# FInal_Board_Tesis_mini_4.net
KiCad netlist of a schematic drawn in EAGLE
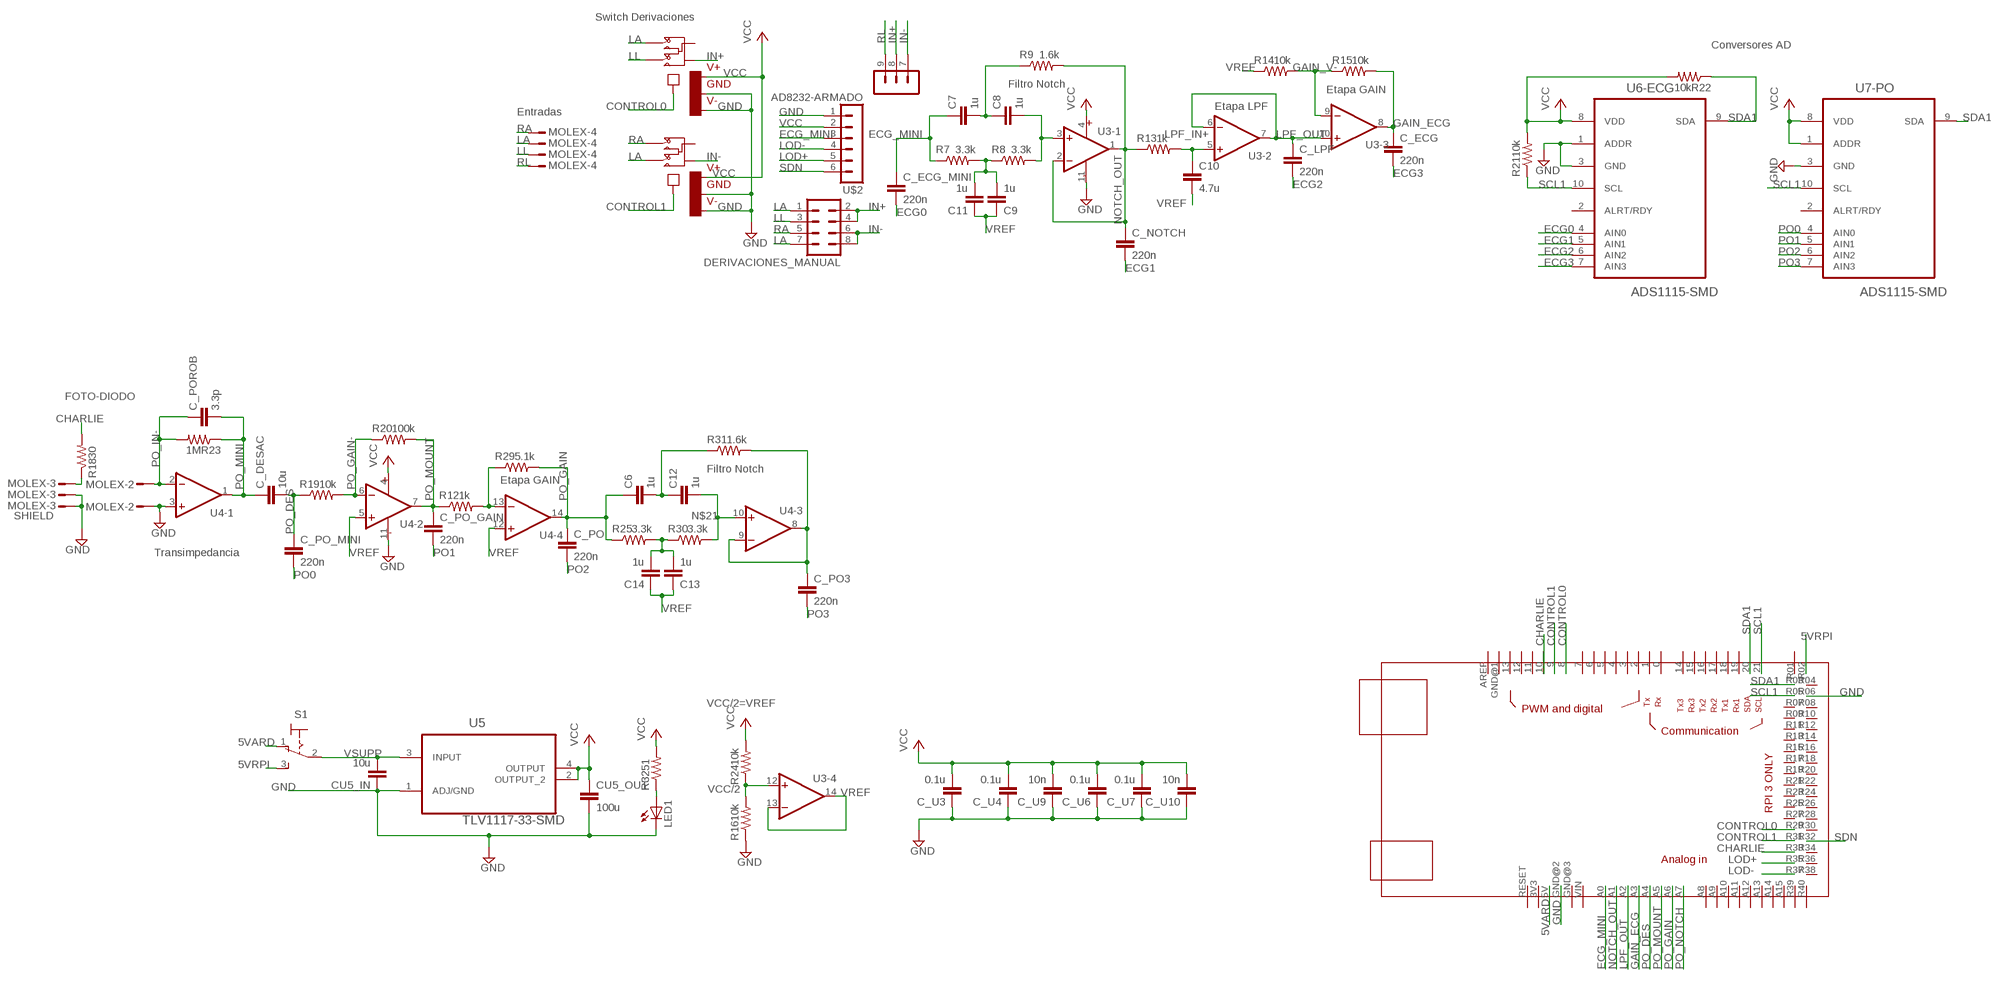
[diagram p0: schematic, sheet 1]

(export (version "E")
  (design (tool "Eeschema 10.0.6"))
  (components
    (comp (ref "C6")
      (value "1u")
      (footprint "eagle-import:C0805")
      (libsource (lib "eagle-import") (part "C-EUC0805"))
    )
    (comp (ref "C7")
      (value "1u")
      (footprint "eagle-import:C0805")
      (libsource (lib "eagle-import") (part "C-EUC0805"))
    )
    (comp (ref "C8")
      (value "1u")
      (footprint "eagle-import:C0805")
      (libsource (lib "eagle-import") (part "C-EUC0805"))
    )
    (comp (ref "C9")
      (value "1u")
      (footprint "eagle-import:C0805")
      (libsource (lib "eagle-import") (part "C-EUC0805"))
    )
    (comp (ref "C10")
      (value "4.7u")
      (footprint "eagle-import:C0805")
      (libsource (lib "eagle-import") (part "C-EUC0805"))
    )
    (comp (ref "C11")
      (value "1u")
      (footprint "eagle-import:C0805")
      (libsource (lib "eagle-import") (part "C-EUC0805"))
    )
    (comp (ref "C12")
      (value "1u")
      (footprint "eagle-import:C0805")
      (libsource (lib "eagle-import") (part "C-EUC0805"))
    )
    (comp (ref "C13")
      (value "1u")
      (footprint "eagle-import:C0805")
      (libsource (lib "eagle-import") (part "C-EUC0805"))
    )
    (comp (ref "C14")
      (value "1u")
      (footprint "eagle-import:C0805")
      (libsource (lib "eagle-import") (part "C-EUC0805"))
    )
    (comp (ref "CU5_IN")
      (value "10u")
      (footprint "eagle-import:C0805")
      (libsource (lib "eagle-import") (part "C-EUC0805"))
    )
    (comp (ref "CU5_OUT")
      (value "100u")
      (footprint "eagle-import:C0805")
      (libsource (lib "eagle-import") (part "C-EUC0805"))
    )
    (comp (ref "C_DESAC")
      (value "10u")
      (footprint "eagle-import:C0805")
      (libsource (lib "eagle-import") (part "C-EUC0805"))
    )
    (comp (ref "C_ECG")
      (value "220n")
      (footprint "eagle-import:C0805")
      (libsource (lib "eagle-import") (part "C-EUC0805"))
    )
    (comp (ref "C_ECG_MINI")
      (value "220n")
      (footprint "eagle-import:C0805")
      (libsource (lib "eagle-import") (part "C-EUC0805"))
    )
    (comp (ref "C_LPF")
      (value "220n")
      (footprint "eagle-import:C0805")
      (libsource (lib "eagle-import") (part "C-EUC0805"))
    )
    (comp (ref "C_NOTCH")
      (value "220n")
      (footprint "eagle-import:C0805")
      (libsource (lib "eagle-import") (part "C-EUC0805"))
    )
    (comp (ref "C_PO")
      (value "220n")
      (footprint "eagle-import:C0805")
      (libsource (lib "eagle-import") (part "C-EUC0805"))
    )
    (comp (ref "C_PO3")
      (value "220n")
      (footprint "eagle-import:C0805")
      (libsource (lib "eagle-import") (part "C-EUC0805"))
    )
    (comp (ref "C_POROB")
      (value "3.3p")
      (footprint "eagle-import:C0805")
      (libsource (lib "eagle-import") (part "C-EUC0805"))
    )
    (comp (ref "C_PO_GAIN")
      (value "220n")
      (footprint "eagle-import:C0805")
      (libsource (lib "eagle-import") (part "C-EUC0805"))
    )
    (comp (ref "C_PO_MINI")
      (value "220n")
      (footprint "eagle-import:C0805")
      (libsource (lib "eagle-import") (part "C-EUC0805"))
    )
    (comp (ref "C_U3")
      (value "0.1u")
      (footprint "eagle-import:C0805")
      (libsource (lib "eagle-import") (part "C-EUC0805"))
    )
    (comp (ref "C_U4")
      (value "0.1u")
      (footprint "eagle-import:C0805")
      (libsource (lib "eagle-import") (part "C-EUC0805"))
    )
    (comp (ref "C_U6")
      (value "0.1u")
      (footprint "eagle-import:C0805")
      (libsource (lib "eagle-import") (part "C-EUC0805"))
    )
    (comp (ref "C_U7")
      (value "0.1u")
      (footprint "eagle-import:C0805")
      (libsource (lib "eagle-import") (part "C-EUC0805"))
    )
    (comp (ref "C_U9")
      (value "10n")
      (footprint "eagle-import:C0805")
      (libsource (lib "eagle-import") (part "C-EUC0805"))
    )
    (comp (ref "C_U10")
      (value "10n")
      (footprint "eagle-import:C0805")
      (libsource (lib "eagle-import") (part "C-EUC0805"))
    )
    (comp (ref "DERIVACIONES_MANUAL")
      (value "MA04-2")
      (footprint "eagle-import:MA04-2")
      (libsource (lib "eagle-import") (part "MA04-2"))
    )
    (comp (ref "LED1")
      (value "LED_E")
      (footprint "eagle-import:LED_1206")
      (libsource (lib "eagle-import") (part "LED_E"))
    )
    (comp (ref "R7")
      (value "3.3k")
      (footprint "eagle-import:M3216")
      (libsource (lib "eagle-import") (part "R-US_M3216"))
    )
    (comp (ref "R8")
      (value "3.3k")
      (footprint "eagle-import:M3216")
      (libsource (lib "eagle-import") (part "R-US_M3216"))
    )
    (comp (ref "R9")
      (value "1.6k")
      (footprint "eagle-import:M3216")
      (libsource (lib "eagle-import") (part "R-US_M3216"))
    )
    (comp (ref "R12")
      (value "1k")
      (footprint "eagle-import:M3216")
      (libsource (lib "eagle-import") (part "R-US_M3216"))
    )
    (comp (ref "R13")
      (value "1k")
      (footprint "eagle-import:M3216")
      (libsource (lib "eagle-import") (part "R-US_M3216"))
    )
    (comp (ref "R14")
      (value "10k")
      (footprint "eagle-import:M3216")
      (libsource (lib "eagle-import") (part "R-US_M3216"))
    )
    (comp (ref "R15")
      (value "10k")
      (footprint "eagle-import:M3216")
      (libsource (lib "eagle-import") (part "R-US_M3216"))
    )
    (comp (ref "R16")
      (value "10k")
      (footprint "eagle-import:M3216")
      (libsource (lib "eagle-import") (part "R-US_M3216"))
    )
    (comp (ref "R18")
      (value "30")
      (footprint "eagle-import:M3216")
      (libsource (lib "eagle-import") (part "R-US_M3216"))
    )
    (comp (ref "R19")
      (value "10k")
      (footprint "eagle-import:M3216")
      (libsource (lib "eagle-import") (part "R-US_M3216"))
    )
    (comp (ref "R20")
      (value "100k")
      (footprint "eagle-import:M3216")
      (libsource (lib "eagle-import") (part "R-US_M3216"))
    )
    (comp (ref "R21")
      (value "10k")
      (footprint "eagle-import:M3216")
      (libsource (lib "eagle-import") (part "R-US_M3216"))
    )
    (comp (ref "R22")
      (value "10k")
      (footprint "eagle-import:M3216")
      (libsource (lib "eagle-import") (part "R-US_M3216"))
    )
    (comp (ref "R23")
      (value "1M")
      (footprint "eagle-import:M3216")
      (libsource (lib "eagle-import") (part "R-US_M3216"))
    )
    (comp (ref "R24")
      (value "10k")
      (footprint "eagle-import:M3216")
      (libsource (lib "eagle-import") (part "R-US_M3216"))
    )
    (comp (ref "R25")
      (value "3.3k")
      (footprint "eagle-import:M3216")
      (libsource (lib "eagle-import") (part "R-US_M3216"))
    )
    (comp (ref "R29")
      (value "5.1k")
      (footprint "eagle-import:M3216")
      (libsource (lib "eagle-import") (part "R-US_M3216"))
    )
    (comp (ref "R30")
      (value "3.3k")
      (footprint "eagle-import:M3216")
      (libsource (lib "eagle-import") (part "R-US_M3216"))
    )
    (comp (ref "R31")
      (value "1.6k")
      (footprint "eagle-import:M3216")
      (libsource (lib "eagle-import") (part "R-US_M3216"))
    )
    (comp (ref "R32")
      (value "51")
      (footprint "eagle-import:M3216")
      (libsource (lib "eagle-import") (part "R-US_M3216"))
    )
    (comp (ref "S1")
      (value "320-916")
      (footprint "eagle-import:320-916")
      (libsource (lib "eagle-import") (part "320-916"))
    )
    (comp (ref "U$1")
      (value "MEGA_DEVICE")
      (footprint "eagle-import:MEGABOX")
      (libsource (lib "eagle-import") (part "MEGA_DEVICE"))
    )
    (comp (ref "U$2")
      (value "AD8232-ARMADO")
      (footprint "eagle-import:PINES-ECG")
      (libsource (lib "eagle-import") (part "AD8232-ARMADO"))
    )
    (comp (ref "U$3")
      (value "MOLEX-3")
      (footprint "eagle-import:MOLEX-3")
      (libsource (lib "eagle-import") (part "MOLEX-3"))
    )
    (comp (ref "U$4")
      (value "MOLEX-2")
      (footprint "eagle-import:MOLEX-2")
      (libsource (lib "eagle-import") (part "MOLEX-2"))
    )
    (comp (ref "U$5")
      (value "MOLEX-4")
      (footprint "eagle-import:MOLEX-4")
      (libsource (lib "eagle-import") (part "MOLEX-4"))
    )
    (comp (ref "U3")
      (value "OPA4348-SMD")
      (footprint "eagle-import:14TSSOP")
      (fields (field (name "MPN") "OPA4348AQPWRQ1"))
      (libsource (lib "eagle-import") (part "OPA4348-SMD"))
    )
    (comp (ref "U4")
      (value "OPA4348-SMD")
      (footprint "eagle-import:14TSSOP")
      (fields (field (name "MPN") "OPA4348AQPWRQ1"))
      (libsource (lib "eagle-import") (part "OPA4348-SMD"))
    )
    (comp (ref "U5")
      (value "TLV1117-33-SMD")
      (footprint "eagle-import:SOT223")
      (fields (field (name "MPN") "TLV1117-33IDCY"))
      (libsource (lib "eagle-import") (part "TLV1117-33-SMD"))
    )
    (comp (ref "U6-ECG")
      (value "ADS1115-SMD")
      (footprint "eagle-import:10MSOP")
      (libsource (lib "eagle-import") (part "ADS1115-SMD"))
    )
    (comp (ref "U7-PO")
      (value "ADS1115-SMD")
      (footprint "eagle-import:10MSOP")
      (libsource (lib "eagle-import") (part "ADS1115-SMD"))
    )
    (comp (ref "U9")
      (value "MAX4528-SMD")
      (footprint "eagle-import:8MSOP-C_PTO")
      (libsource (lib "eagle-import") (part "MAX4528-SMD"))
    )
    (comp (ref "U10")
      (value "MAX4528-SMD")
      (footprint "eagle-import:8MSOP-C_PTO")
      (libsource (lib "eagle-import") (part "MAX4528-SMD"))
    )
  )
  (nets
    (net (code "1") (name "/5VARD") (class "Default")
      (node (ref "S1") (pin "1") (pinfunction "O_1") (pintype "passive"))
      (node (ref "U$1") (pin "5V") (pinfunction "5V_5V") (pintype "bidirectional"))
    )
    (net (code "2") (name "/5VRPI") (class "Default")
      (node (ref "S1") (pin "3") (pinfunction "S_3") (pintype "passive"))
      (node (ref "U$1") (pin "R02") (pinfunction "5V1_R02") (pintype "bidirectional"))
    )
    (net (code "3") (name "/CHARLIE") (class "Default")
      (node (ref "R18") (pin "2") (pinfunction "2_2") (pintype "passive"))
      (node (ref "U$1") (pin "10") (pinfunction "10_10") (pintype "bidirectional"))
      (node (ref "U$1") (pin "R33") (pinfunction "GPIO13_R33") (pintype "bidirectional"))
    )
    (net (code "4") (name "/CONTROL0") (class "Default")
      (node (ref "U$1") (pin "8") (pinfunction "8_8") (pintype "bidirectional"))
      (node (ref "U$1") (pin "R29") (pinfunction "GPIO5_R29") (pintype "bidirectional"))
      (node (ref "U9") (pin "4") (pinfunction "IN_4") (pintype "bidirectional"))
    )
    (net (code "5") (name "/CONTROL1") (class "Default")
      (node (ref "U$1") (pin "9") (pinfunction "9_9") (pintype "bidirectional"))
      (node (ref "U$1") (pin "R31") (pinfunction "GPIO6_R31") (pintype "bidirectional"))
      (node (ref "U10") (pin "4") (pinfunction "IN_4") (pintype "bidirectional"))
    )
    (net (code "6") (name "/ECG0") (class "Default")
      (node (ref "C_ECG_MINI") (pin "2") (pinfunction "2_2") (pintype "passive"))
      (node (ref "U6-ECG") (pin "4") (pinfunction "AIN0_4") (pintype "input"))
    )
    (net (code "7") (name "/ECG1") (class "Default")
      (node (ref "C_NOTCH") (pin "2") (pinfunction "2_2") (pintype "passive"))
      (node (ref "U6-ECG") (pin "5") (pinfunction "AIN1_5") (pintype "input"))
    )
    (net (code "8") (name "/ECG2") (class "Default")
      (node (ref "C_LPF") (pin "2") (pinfunction "2_2") (pintype "passive"))
      (node (ref "U6-ECG") (pin "6") (pinfunction "AIN2_6") (pintype "input"))
    )
    (net (code "9") (name "/ECG3") (class "Default")
      (node (ref "C_ECG") (pin "2") (pinfunction "2_2") (pintype "passive"))
      (node (ref "U6-ECG") (pin "7") (pinfunction "AIN3_7") (pintype "input"))
    )
    (net (code "10") (name "/ECG_MINI") (class "Default")
      (node (ref "C7") (pin "1") (pinfunction "1_1") (pintype "passive"))
      (node (ref "C_ECG_MINI") (pin "1") (pinfunction "1_1") (pintype "passive"))
      (node (ref "R7") (pin "1") (pinfunction "1_1") (pintype "passive"))
      (node (ref "U$1") (pin "A0") (pinfunction "A0_A0") (pintype "bidirectional"))
      (node (ref "U$2") (pin "3") (pinfunction "OUT_3") (pintype "passive"))
    )
    (net (code "11") (name "/GAIN_ECG") (class "Default")
      (node (ref "C_ECG") (pin "1") (pinfunction "1_1") (pintype "passive"))
      (node (ref "R15") (pin "2") (pinfunction "2_2") (pintype "passive"))
      (node (ref "U$1") (pin "A3") (pinfunction "A3_A3") (pintype "bidirectional"))
      (node (ref "U3") (pin "8") (pinfunction "OUT_8") (pintype "open_collector"))
    )
    (net (code "12") (name "/GAIN_V-") (class "Default")
      (node (ref "R14") (pin "2") (pinfunction "2_2") (pintype "passive"))
      (node (ref "R15") (pin "1") (pinfunction "1_1") (pintype "passive"))
      (node (ref "U3") (pin "9") (pinfunction "-IN_9") (pintype "input"))
    )
    (net (code "13") (name "/IN+") (class "Default")
      (node (ref "DERIVACIONES_MANUAL") (pin "2") (pinfunction "2_2") (pintype "passive"))
      (node (ref "DERIVACIONES_MANUAL") (pin "4") (pinfunction "4_4") (pintype "passive"))
      (node (ref "U$2") (pin "8") (pinfunction "LA_8") (pintype "passive"))
      (node (ref "U9") (pin "6") (pinfunction "Y_6") (pintype "bidirectional"))
    )
    (net (code "14") (name "/IN-") (class "Default")
      (node (ref "DERIVACIONES_MANUAL") (pin "6") (pinfunction "6_6") (pintype "passive"))
      (node (ref "DERIVACIONES_MANUAL") (pin "8") (pinfunction "8_8") (pintype "passive"))
      (node (ref "U$2") (pin "7") (pinfunction "RA_7") (pintype "passive"))
      (node (ref "U10") (pin "6") (pinfunction "Y_6") (pintype "bidirectional"))
    )
    (net (code "15") (name "/LA") (class "Default")
      (node (ref "DERIVACIONES_MANUAL") (pin "1") (pinfunction "1_1") (pintype "passive"))
      (node (ref "DERIVACIONES_MANUAL") (pin "7") (pinfunction "7_7") (pintype "passive"))
      (node (ref "U$5") (pin "2") (pinfunction "S_2") (pintype "passive"))
      (node (ref "U10") (pin "2") (pinfunction "B_2") (pintype "bidirectional"))
      (node (ref "U9") (pin "1") (pinfunction "A_1") (pintype "bidirectional"))
    )
    (net (code "16") (name "/LL") (class "Default")
      (node (ref "DERIVACIONES_MANUAL") (pin "3") (pinfunction "3_3") (pintype "passive"))
      (node (ref "U$5") (pin "3") (pinfunction "S_3") (pintype "passive"))
      (node (ref "U9") (pin "2") (pinfunction "B_2") (pintype "bidirectional"))
    )
    (net (code "17") (name "/LOD+") (class "Default")
      (node (ref "U$1") (pin "R35") (pinfunction "GPIO19_R35") (pintype "bidirectional"))
      (node (ref "U$2") (pin "5") (pinfunction "LOD+_5") (pintype "passive"))
    )
    (net (code "18") (name "/LOD-") (class "Default")
      (node (ref "U$1") (pin "R37") (pinfunction "GPIO26_R37") (pintype "bidirectional"))
      (node (ref "U$2") (pin "4") (pinfunction "LOD-_4") (pintype "passive"))
    )
    (net (code "19") (name "/LPF_IN+") (class "Default")
      (node (ref "C10") (pin "1") (pinfunction "1_1") (pintype "passive"))
      (node (ref "R13") (pin "2") (pinfunction "2_2") (pintype "passive"))
      (node (ref "U3") (pin "5") (pinfunction "+IN_5") (pintype "input"))
    )
    (net (code "20") (name "/LPF_OUT") (class "Default")
      (node (ref "C_LPF") (pin "1") (pinfunction "1_1") (pintype "passive"))
      (node (ref "U$1") (pin "A2") (pinfunction "A2_A2") (pintype "bidirectional"))
      (node (ref "U3") (pin "10") (pinfunction "+IN_10") (pintype "input"))
      (node (ref "U3") (pin "6") (pinfunction "-IN_6") (pintype "input"))
      (node (ref "U3") (pin "7") (pinfunction "OUT_7") (pintype "open_collector"))
    )
    (net (code "21") (name "/N$21") (class "Default")
      (node (ref "C12") (pin "2") (pinfunction "2_2") (pintype "passive"))
      (node (ref "R30") (pin "2") (pinfunction "2_2") (pintype "passive"))
      (node (ref "U4") (pin "10") (pinfunction "+IN_10") (pintype "input"))
    )
    (net (code "22") (name "/NOTCH_OUT") (class "Default")
      (node (ref "C_NOTCH") (pin "1") (pinfunction "1_1") (pintype "passive"))
      (node (ref "R13") (pin "1") (pinfunction "1_1") (pintype "passive"))
      (node (ref "R9") (pin "2") (pinfunction "2_2") (pintype "passive"))
      (node (ref "U$1") (pin "A1") (pinfunction "A1_A1") (pintype "bidirectional"))
      (node (ref "U3") (pin "1") (pinfunction "OUT_1") (pintype "open_collector"))
      (node (ref "U3") (pin "2") (pinfunction "-IN_2") (pintype "input"))
    )
    (net (code "23") (name "/PO0") (class "Default")
      (node (ref "C_PO_MINI") (pin "2") (pinfunction "2_2") (pintype "passive"))
      (node (ref "U7-PO") (pin "4") (pinfunction "AIN0_4") (pintype "input"))
    )
    (net (code "24") (name "/PO1") (class "Default")
      (node (ref "C_PO_GAIN") (pin "2") (pinfunction "2_2") (pintype "passive"))
      (node (ref "U7-PO") (pin "5") (pinfunction "AIN1_5") (pintype "input"))
    )
    (net (code "25") (name "/PO2") (class "Default")
      (node (ref "C_PO") (pin "2") (pinfunction "2_2") (pintype "passive"))
      (node (ref "U7-PO") (pin "6") (pinfunction "AIN2_6") (pintype "input"))
    )
    (net (code "26") (name "/PO3") (class "Default")
      (node (ref "C_PO3") (pin "2") (pinfunction "2_2") (pintype "passive"))
      (node (ref "U7-PO") (pin "7") (pinfunction "AIN3_7") (pintype "input"))
    )
    (net (code "27") (name "/PO_DES") (class "Default")
      (node (ref "C_DESAC") (pin "2") (pinfunction "2_2") (pintype "passive"))
      (node (ref "C_PO_MINI") (pin "1") (pinfunction "1_1") (pintype "passive"))
      (node (ref "R19") (pin "1") (pinfunction "1_1") (pintype "passive"))
      (node (ref "U$1") (pin "A4") (pinfunction "A4_A4") (pintype "bidirectional"))
    )
    (net (code "28") (name "/PO_GAIN") (class "Default")
      (node (ref "C6") (pin "1") (pinfunction "1_1") (pintype "passive"))
      (node (ref "C_PO") (pin "1") (pinfunction "1_1") (pintype "passive"))
      (node (ref "R25") (pin "1") (pinfunction "1_1") (pintype "passive"))
      (node (ref "R29") (pin "2") (pinfunction "2_2") (pintype "passive"))
      (node (ref "U$1") (pin "A6") (pinfunction "A6_A6") (pintype "bidirectional"))
      (node (ref "U4") (pin "14") (pinfunction "OUT_14") (pintype "open_collector"))
    )
    (net (code "29") (name "/PO_GAIN-") (class "Default")
      (node (ref "R19") (pin "2") (pinfunction "2_2") (pintype "passive"))
      (node (ref "R20") (pin "1") (pinfunction "1_1") (pintype "passive"))
      (node (ref "U4") (pin "6") (pinfunction "-IN_6") (pintype "input"))
    )
    (net (code "30") (name "/PO_IN-") (class "Default")
      (node (ref "C_POROB") (pin "1") (pinfunction "1_1") (pintype "passive"))
      (node (ref "R23") (pin "2") (pinfunction "2_2") (pintype "passive"))
      (node (ref "U$4") (pin "1") (pinfunction "S_1") (pintype "passive"))
      (node (ref "U4") (pin "2") (pinfunction "-IN_2") (pintype "input"))
    )
    (net (code "31") (name "/PO_MINI") (class "Default")
      (node (ref "C_DESAC") (pin "1") (pinfunction "1_1") (pintype "passive"))
      (node (ref "C_POROB") (pin "2") (pinfunction "2_2") (pintype "passive"))
      (node (ref "R23") (pin "1") (pinfunction "1_1") (pintype "passive"))
      (node (ref "U4") (pin "1") (pinfunction "OUT_1") (pintype "open_collector"))
    )
    (net (code "32") (name "/PO_MOUNT") (class "Default")
      (node (ref "C_PO_GAIN") (pin "1") (pinfunction "1_1") (pintype "passive"))
      (node (ref "R12") (pin "1") (pinfunction "1_1") (pintype "passive"))
      (node (ref "R20") (pin "2") (pinfunction "2_2") (pintype "passive"))
      (node (ref "U$1") (pin "A5") (pinfunction "A5_A5") (pintype "bidirectional"))
      (node (ref "U4") (pin "7") (pinfunction "OUT_7") (pintype "open_collector"))
    )
    (net (code "33") (name "/PO_NOTCH") (class "Default")
      (node (ref "C_PO3") (pin "1") (pinfunction "1_1") (pintype "passive"))
      (node (ref "R31") (pin "2") (pinfunction "2_2") (pintype "passive"))
      (node (ref "U$1") (pin "A7") (pinfunction "A7_A7") (pintype "bidirectional"))
      (node (ref "U4") (pin "8") (pinfunction "OUT_8") (pintype "open_collector"))
      (node (ref "U4") (pin "9") (pinfunction "-IN_9") (pintype "input"))
    )
    (net (code "34") (name "/RA") (class "Default")
      (node (ref "DERIVACIONES_MANUAL") (pin "5") (pinfunction "5_5") (pintype "passive"))
      (node (ref "U$5") (pin "1") (pinfunction "S_1") (pintype "passive"))
      (node (ref "U10") (pin "1") (pinfunction "A_1") (pintype "bidirectional"))
    )
    (net (code "35") (name "/RL") (class "Default")
      (node (ref "U$2") (pin "9") (pinfunction "RL_9") (pintype "passive"))
      (node (ref "U$5") (pin "4") (pinfunction "S_4") (pintype "passive"))
    )
    (net (code "36") (name "/SCL1") (class "Default")
      (node (ref "R21") (pin "1") (pinfunction "1_1") (pintype "passive"))
      (node (ref "U$1") (pin "21") (pinfunction "21_21") (pintype "bidirectional"))
      (node (ref "U$1") (pin "R05") (pinfunction "SCL1_R05") (pintype "bidirectional"))
      (node (ref "U6-ECG") (pin "10") (pinfunction "SCL_10") (pintype "input"))
      (node (ref "U7-PO") (pin "10") (pinfunction "SCL_10") (pintype "input"))
    )
    (net (code "37") (name "/SDA1") (class "Default")
      (node (ref "R22") (pin "1") (pinfunction "1_1") (pintype "passive"))
      (node (ref "U$1") (pin "20") (pinfunction "20_20") (pintype "bidirectional"))
      (node (ref "U$1") (pin "R03") (pinfunction "SDA1_R03") (pintype "bidirectional"))
      (node (ref "U6-ECG") (pin "9") (pinfunction "SDA_9") (pintype "bidirectional"))
      (node (ref "U7-PO") (pin "9") (pinfunction "SDA_9") (pintype "bidirectional"))
    )
    (net (code "38") (name "/SDN") (class "Default")
      (node (ref "U$1") (pin "R32") (pinfunction "GPIO12_R32") (pintype "bidirectional"))
      (node (ref "U$2") (pin "6") (pinfunction "~{SDN}_6") (pintype "passive"))
    )
    (net (code "39") (name "/VCC{slash}2") (class "Default")
      (node (ref "R16") (pin "2") (pinfunction "2_2") (pintype "passive"))
      (node (ref "R24") (pin "1") (pinfunction "1_1") (pintype "passive"))
      (node (ref "U3") (pin "12") (pinfunction "+IN_12") (pintype "input"))
    )
    (net (code "40") (name "/VREF") (class "Default")
      (node (ref "C10") (pin "2") (pinfunction "2_2") (pintype "passive"))
      (node (ref "C11") (pin "1") (pinfunction "1_1") (pintype "passive"))
      (node (ref "C13") (pin "1") (pinfunction "1_1") (pintype "passive"))
      (node (ref "C14") (pin "1") (pinfunction "1_1") (pintype "passive"))
      (node (ref "C9") (pin "1") (pinfunction "1_1") (pintype "passive"))
      (node (ref "R14") (pin "1") (pinfunction "1_1") (pintype "passive"))
      (node (ref "U3") (pin "13") (pinfunction "-IN_13") (pintype "input"))
      (node (ref "U3") (pin "14") (pinfunction "OUT_14") (pintype "open_collector"))
      (node (ref "U4") (pin "12") (pinfunction "+IN_12") (pintype "input"))
      (node (ref "U4") (pin "5") (pinfunction "+IN_5") (pintype "input"))
    )
    (net (code "41") (name "/VSUPP") (class "Default")
      (node (ref "CU5_IN") (pin "2") (pinfunction "2_2") (pintype "passive"))
      (node (ref "S1") (pin "2") (pinfunction "P_2") (pintype "passive"))
      (node (ref "U5") (pin "3") (pinfunction "INPUT_3") (pintype "input"))
    )
    (net (code "42") (name "GND") (class "Default")
      (node (ref "CU5_IN") (pin "1") (pinfunction "1_1") (pintype "passive"))
      (node (ref "CU5_OUT") (pin "2") (pinfunction "2_2") (pintype "passive"))
      (node (ref "C_U10") (pin "1") (pinfunction "1_1") (pintype "passive"))
      (node (ref "C_U3") (pin "1") (pinfunction "1_1") (pintype "passive"))
      (node (ref "C_U4") (pin "1") (pinfunction "1_1") (pintype "passive"))
      (node (ref "C_U6") (pin "1") (pinfunction "1_1") (pintype "passive"))
      (node (ref "C_U7") (pin "1") (pinfunction "1_1") (pintype "passive"))
      (node (ref "C_U9") (pin "1") (pinfunction "1_1") (pintype "passive"))
      (node (ref "LED1") (pin "C") (pinfunction "C_C") (pintype "passive"))
      (node (ref "R16") (pin "1") (pinfunction "1_1") (pintype "passive"))
      (node (ref "U$1") (pin "GND@2") (pinfunction "GND_GND@2") (pintype "bidirectional"))
      (node (ref "U$1") (pin "R06") (pinfunction "GND_R06") (pintype "bidirectional"))
      (node (ref "U$2") (pin "1") (pinfunction "GND_1") (pintype "passive"))
      (node (ref "U$3") (pin "2") (pinfunction "S_2") (pintype "passive"))
      (node (ref "U$3") (pin "3") (pinfunction "S_3") (pintype "passive"))
      (node (ref "U$4") (pin "2") (pinfunction "S_2") (pintype "passive"))
      (node (ref "U10") (pin "3") (pinfunction "GND_3") (pintype "bidirectional"))
      (node (ref "U10") (pin "5") (pinfunction "V-_5") (pintype "bidirectional"))
      (node (ref "U3") (pin "11") (pinfunction "V-_11") (pintype "power_in"))
      (node (ref "U4") (pin "11") (pinfunction "V-_11") (pintype "power_in"))
      (node (ref "U4") (pin "3") (pinfunction "+IN_3") (pintype "input"))
      (node (ref "U5") (pin "1") (pinfunction "ADJ/GND_1") (pintype "input"))
      (node (ref "U6-ECG") (pin "1") (pinfunction "ADDR_1") (pintype "input"))
      (node (ref "U6-ECG") (pin "3") (pinfunction "GND_3") (pintype "passive"))
      (node (ref "U7-PO") (pin "3") (pinfunction "GND_3") (pintype "passive"))
      (node (ref "U9") (pin "3") (pinfunction "GND_3") (pintype "bidirectional"))
      (node (ref "U9") (pin "5") (pinfunction "V-_5") (pintype "bidirectional"))
    )
    (net (code "43") (name "Net-(C7-Pad2)") (class "Default")
      (node (ref "C7") (pin "2") (pinfunction "2_2") (pintype "passive"))
      (node (ref "C8") (pin "1") (pinfunction "1_1") (pintype "passive"))
      (node (ref "R9") (pin "1") (pinfunction "1_1") (pintype "passive"))
    )
    (net (code "44") (name "Net-(C11-Pad2)") (class "Default")
      (node (ref "C11") (pin "2") (pinfunction "2_2") (pintype "passive"))
      (node (ref "C9") (pin "2") (pinfunction "2_2") (pintype "passive"))
      (node (ref "R7") (pin "2") (pinfunction "2_2") (pintype "passive"))
      (node (ref "R8") (pin "1") (pinfunction "1_1") (pintype "passive"))
    )
    (net (code "45") (name "Net-(C12-Pad1)") (class "Default")
      (node (ref "C12") (pin "1") (pinfunction "1_1") (pintype "passive"))
      (node (ref "C6") (pin "2") (pinfunction "2_2") (pintype "passive"))
      (node (ref "R31") (pin "1") (pinfunction "1_1") (pintype "passive"))
    )
    (net (code "46") (name "Net-(C13-Pad2)") (class "Default")
      (node (ref "C13") (pin "2") (pinfunction "2_2") (pintype "passive"))
      (node (ref "C14") (pin "2") (pinfunction "2_2") (pintype "passive"))
      (node (ref "R25") (pin "2") (pinfunction "2_2") (pintype "passive"))
      (node (ref "R30") (pin "1") (pinfunction "1_1") (pintype "passive"))
    )
    (net (code "47") (name "Net-(LED1-PadA)") (class "Default")
      (node (ref "LED1") (pin "A") (pinfunction "A_A") (pintype "passive"))
      (node (ref "R32") (pin "1") (pinfunction "1_1") (pintype "passive"))
    )
    (net (code "48") (name "Net-(U$3A-S)") (class "Default")
      (node (ref "R18") (pin "1") (pinfunction "1_1") (pintype "passive"))
      (node (ref "U$3") (pin "1") (pinfunction "S_1") (pintype "passive"))
    )
    (net (code "49") (name "Net-(U3A-+IN)") (class "Default")
      (node (ref "C8") (pin "2") (pinfunction "2_2") (pintype "passive"))
      (node (ref "R8") (pin "2") (pinfunction "2_2") (pintype "passive"))
      (node (ref "U3") (pin "3") (pinfunction "+IN_3") (pintype "input"))
    )
    (net (code "50") (name "Net-(U4D--IN)") (class "Default")
      (node (ref "R12") (pin "2") (pinfunction "2_2") (pintype "passive"))
      (node (ref "R29") (pin "1") (pinfunction "1_1") (pintype "passive"))
      (node (ref "U4") (pin "13") (pinfunction "-IN_13") (pintype "input"))
    )
    (net (code "51") (name "VCC") (class "Default")
      (node (ref "CU5_OUT") (pin "1") (pinfunction "1_1") (pintype "passive"))
      (node (ref "C_U10") (pin "2") (pinfunction "2_2") (pintype "passive"))
      (node (ref "C_U3") (pin "2") (pinfunction "2_2") (pintype "passive"))
      (node (ref "C_U4") (pin "2") (pinfunction "2_2") (pintype "passive"))
      (node (ref "C_U6") (pin "2") (pinfunction "2_2") (pintype "passive"))
      (node (ref "C_U7") (pin "2") (pinfunction "2_2") (pintype "passive"))
      (node (ref "C_U9") (pin "2") (pinfunction "2_2") (pintype "passive"))
      (node (ref "R21") (pin "2") (pinfunction "2_2") (pintype "passive"))
      (node (ref "R22") (pin "2") (pinfunction "2_2") (pintype "passive"))
      (node (ref "R24") (pin "2") (pinfunction "2_2") (pintype "passive"))
      (node (ref "R32") (pin "2") (pinfunction "2_2") (pintype "passive"))
      (node (ref "U$2") (pin "2") (pinfunction "3.3V_2") (pintype "passive"))
      (node (ref "U10") (pin "8") (pinfunction "V+_8") (pintype "bidirectional"))
      (node (ref "U3") (pin "4") (pinfunction "V+_4") (pintype "power_in"))
      (node (ref "U4") (pin "4") (pinfunction "V+_4") (pintype "power_in"))
      (node (ref "U5") (pin "2") (pinfunction "OUTPUT_2_2") (pintype "output"))
      (node (ref "U5") (pin "4") (pinfunction "OUTPUT_4") (pintype "output"))
      (node (ref "U6-ECG") (pin "8") (pinfunction "VDD_8") (pintype "power_in"))
      (node (ref "U7-PO") (pin "1") (pinfunction "ADDR_1") (pintype "input"))
      (node (ref "U7-PO") (pin "8") (pinfunction "VDD_8") (pintype "power_in"))
      (node (ref "U9") (pin "8") (pinfunction "V+_8") (pintype "bidirectional"))
    )
    (net (code "52") (name "unconnected-(U$1-3.3V-PadR01)") (class "Default")
      (node (ref "U$1") (pin "R01") (pinfunction "3.3V_R01") (pintype "bidirectional"))
    )
    (net (code "53") (name "unconnected-(U$1-3.3V-PadR17)") (class "Default")
      (node (ref "U$1") (pin "R17") (pinfunction "3.3V_R17") (pintype "bidirectional"))
    )
    (net (code "54") (name "unconnected-(U$1-5V2-PadR04)") (class "Default")
      (node (ref "U$1") (pin "R04") (pinfunction "5V2_R04") (pintype "bidirectional"))
    )
    (net (code "55") (name "unconnected-(U$1-GCLK-PadR07)") (class "Default")
      (node (ref "U$1") (pin "R07") (pinfunction "GCLK_R07") (pintype "bidirectional"))
    )
    (net (code "56") (name "unconnected-(U$1-GEN0-PadR11)") (class "Default")
      (node (ref "U$1") (pin "R11") (pinfunction "GEN0_R11") (pintype "bidirectional"))
    )
    (net (code "57") (name "unconnected-(U$1-GEN1-PadR12)") (class "Default")
      (node (ref "U$1") (pin "R12") (pinfunction "GEN1_R12") (pintype "bidirectional"))
    )
    (net (code "58") (name "unconnected-(U$1-GEN2-PadR13)") (class "Default")
      (node (ref "U$1") (pin "R13") (pinfunction "GEN2_R13") (pintype "bidirectional"))
    )
    (net (code "59") (name "unconnected-(U$1-GEN3-PadR15)") (class "Default")
      (node (ref "U$1") (pin "R15") (pinfunction "GEN3_R15") (pintype "bidirectional"))
    )
    (net (code "60") (name "unconnected-(U$1-GEN4-PadR16)") (class "Default")
      (node (ref "U$1") (pin "R16") (pinfunction "GEN4_R16") (pintype "bidirectional"))
    )
    (net (code "61") (name "unconnected-(U$1-GEN5-PadR18)") (class "Default")
      (node (ref "U$1") (pin "R18") (pinfunction "GEN5_R18") (pintype "bidirectional"))
    )
    (net (code "62") (name "unconnected-(U$1-GEN6-PadR22)") (class "Default")
      (node (ref "U$1") (pin "R22") (pinfunction "GEN6_R22") (pintype "bidirectional"))
    )
    (net (code "63") (name "unconnected-(U$1-GND-PadGND@1)") (class "Default")
      (node (ref "U$1") (pin "GND@1") (pinfunction "GND_GND@1") (pintype "bidirectional"))
    )
    (net (code "64") (name "unconnected-(U$1-GND-PadGND@3)") (class "Default")
      (node (ref "U$1") (pin "GND@3") (pinfunction "GND_GND@3") (pintype "bidirectional"))
    )
    (net (code "65") (name "unconnected-(U$1-GND-PadR09)") (class "Default")
      (node (ref "U$1") (pin "R09") (pinfunction "GND_R09") (pintype "bidirectional"))
    )
    (net (code "66") (name "unconnected-(U$1-GND-PadR14)") (class "Default")
      (node (ref "U$1") (pin "R14") (pinfunction "GND_R14") (pintype "bidirectional"))
    )
    (net (code "67") (name "unconnected-(U$1-GND-PadR20)") (class "Default")
      (node (ref "U$1") (pin "R20") (pinfunction "GND_R20") (pintype "bidirectional"))
    )
    (net (code "68") (name "unconnected-(U$1-GND-PadR25)") (class "Default")
      (node (ref "U$1") (pin "R25") (pinfunction "GND_R25") (pintype "bidirectional"))
    )
    (net (code "69") (name "unconnected-(U$1-GND-PadR30)") (class "Default")
      (node (ref "U$1") (pin "R30") (pinfunction "GND_R30") (pintype "bidirectional"))
    )
    (net (code "70") (name "unconnected-(U$1-GND-PadR34)") (class "Default")
      (node (ref "U$1") (pin "R34") (pinfunction "GND_R34") (pintype "bidirectional"))
    )
    (net (code "71") (name "unconnected-(U$1-GND-PadR39)") (class "Default")
      (node (ref "U$1") (pin "R39") (pinfunction "GND_R39") (pintype "bidirectional"))
    )
    (net (code "72") (name "unconnected-(U$1-GPIO16-PadR36)") (class "Default")
      (node (ref "U$1") (pin "R36") (pinfunction "GPIO16_R36") (pintype "bidirectional"))
    )
    (net (code "73") (name "unconnected-(U$1-GPIO20-PadR38)") (class "Default")
      (node (ref "U$1") (pin "R38") (pinfunction "GPIO20_R38") (pintype "bidirectional"))
    )
    (net (code "74") (name "unconnected-(U$1-GPIO21-PadR40)") (class "Default")
      (node (ref "U$1") (pin "R40") (pinfunction "GPIO21_R40") (pintype "bidirectional"))
    )
    (net (code "75") (name "unconnected-(U$1-ID_SC-PadR28)") (class "Default")
      (node (ref "U$1") (pin "R28") (pinfunction "ID_SC_R28") (pintype "bidirectional"))
    )
    (net (code "76") (name "unconnected-(U$1-ID_SD-PadR27)") (class "Default")
      (node (ref "U$1") (pin "R27") (pinfunction "ID_SD_R27") (pintype "bidirectional"))
    )
    (net (code "77") (name "unconnected-(U$1-Pad0)") (class "Default")
      (node (ref "U$1") (pin "0") (pinfunction "0_0") (pintype "bidirectional"))
    )
    (net (code "78") (name "unconnected-(U$1-Pad1)") (class "Default")
      (node (ref "U$1") (pin "1") (pinfunction "1_1") (pintype "bidirectional"))
    )
    (net (code "79") (name "unconnected-(U$1-Pad2)") (class "Default")
      (node (ref "U$1") (pin "2") (pinfunction "2_2") (pintype "bidirectional"))
    )
    (net (code "80") (name "unconnected-(U$1-Pad3)") (class "Default")
      (node (ref "U$1") (pin "3") (pinfunction "3_3") (pintype "bidirectional"))
    )
    (net (code "81") (name "unconnected-(U$1-Pad3V3)") (class "Default")
      (node (ref "U$1") (pin "3V3") (pinfunction "3V3_3V3") (pintype "bidirectional"))
    )
    (net (code "82") (name "unconnected-(U$1-Pad4)") (class "Default")
      (node (ref "U$1") (pin "4") (pinfunction "4_4") (pintype "bidirectional"))
    )
    (net (code "83") (name "unconnected-(U$1-Pad5)") (class "Default")
      (node (ref "U$1") (pin "5") (pinfunction "5_5") (pintype "bidirectional"))
    )
    (net (code "84") (name "unconnected-(U$1-Pad6)") (class "Default")
      (node (ref "U$1") (pin "6") (pinfunction "6_6") (pintype "bidirectional"))
    )
    (net (code "85") (name "unconnected-(U$1-Pad7)") (class "Default")
      (node (ref "U$1") (pin "7") (pinfunction "7_7") (pintype "bidirectional"))
    )
    (net (code "86") (name "unconnected-(U$1-Pad11)") (class "Default")
      (node (ref "U$1") (pin "11") (pinfunction "11_11") (pintype "bidirectional"))
    )
    (net (code "87") (name "unconnected-(U$1-Pad12)") (class "Default")
      (node (ref "U$1") (pin "12") (pinfunction "12_12") (pintype "bidirectional"))
    )
    (net (code "88") (name "unconnected-(U$1-Pad13)") (class "Default")
      (node (ref "U$1") (pin "13") (pinfunction "13_13") (pintype "bidirectional"))
    )
    (net (code "89") (name "unconnected-(U$1-Pad14)") (class "Default")
      (node (ref "U$1") (pin "14") (pinfunction "14_14") (pintype "bidirectional"))
    )
    (net (code "90") (name "unconnected-(U$1-Pad15)") (class "Default")
      (node (ref "U$1") (pin "15") (pinfunction "15_15") (pintype "bidirectional"))
    )
    (net (code "91") (name "unconnected-(U$1-Pad16)") (class "Default")
      (node (ref "U$1") (pin "16") (pinfunction "16_16") (pintype "bidirectional"))
    )
    (net (code "92") (name "unconnected-(U$1-Pad17)") (class "Default")
      (node (ref "U$1") (pin "17") (pinfunction "17_17") (pintype "bidirectional"))
    )
    (net (code "93") (name "unconnected-(U$1-Pad18)") (class "Default")
      (node (ref "U$1") (pin "18") (pinfunction "18_18") (pintype "bidirectional"))
    )
    (net (code "94") (name "unconnected-(U$1-Pad19)") (class "Default")
      (node (ref "U$1") (pin "19") (pinfunction "19_19") (pintype "bidirectional"))
    )
    (net (code "95") (name "unconnected-(U$1-PadA8)") (class "Default")
      (node (ref "U$1") (pin "A8") (pinfunction "A8_A8") (pintype "bidirectional"))
    )
    (net (code "96") (name "unconnected-(U$1-PadA9)") (class "Default")
      (node (ref "U$1") (pin "A9") (pinfunction "A9_A9") (pintype "bidirectional"))
    )
    (net (code "97") (name "unconnected-(U$1-PadA10)") (class "Default")
      (node (ref "U$1") (pin "A10") (pinfunction "A10_A10") (pintype "bidirectional"))
    )
    (net (code "98") (name "unconnected-(U$1-PadA11)") (class "Default")
      (node (ref "U$1") (pin "A11") (pinfunction "A11_A11") (pintype "bidirectional"))
    )
    (net (code "99") (name "unconnected-(U$1-PadA12)") (class "Default")
      (node (ref "U$1") (pin "A12") (pinfunction "A12_A12") (pintype "bidirectional"))
    )
    (net (code "100") (name "unconnected-(U$1-PadA13)") (class "Default")
      (node (ref "U$1") (pin "A13") (pinfunction "A13_A13") (pintype "bidirectional"))
    )
    (net (code "101") (name "unconnected-(U$1-PadA14)") (class "Default")
      (node (ref "U$1") (pin "A14") (pinfunction "A14_A14") (pintype "bidirectional"))
    )
    (net (code "102") (name "unconnected-(U$1-PadA15)") (class "Default")
      (node (ref "U$1") (pin "A15") (pinfunction "A15_A15") (pintype "bidirectional"))
    )
    (net (code "103") (name "unconnected-(U$1-PadAREF)") (class "Default")
      (node (ref "U$1") (pin "AREF") (pinfunction "AREF_AREF") (pintype "bidirectional"))
    )
    (net (code "104") (name "unconnected-(U$1-PadRESET)") (class "Default")
      (node (ref "U$1") (pin "RESET") (pinfunction "RESET_RESET") (pintype "bidirectional"))
    )
    (net (code "105") (name "unconnected-(U$1-PadVIN)") (class "Default")
      (node (ref "U$1") (pin "VIN") (pinfunction "VIN_VIN") (pintype "bidirectional"))
    )
    (net (code "106") (name "unconnected-(U$1-RXD0-PadR10)") (class "Default")
      (node (ref "U$1") (pin "R10") (pinfunction "RXD0_R10") (pintype "bidirectional"))
    )
    (net (code "107") (name "unconnected-(U$1-SPI_CE0_N-PadR24)") (class "Default")
      (node (ref "U$1") (pin "R24") (pinfunction "SPI_CE0_N_R24") (pintype "bidirectional"))
    )
    (net (code "108") (name "unconnected-(U$1-SPI_CE1_N-PadR26)") (class "Default")
      (node (ref "U$1") (pin "R26") (pinfunction "SPI_CE1_N_R26") (pintype "bidirectional"))
    )
    (net (code "109") (name "unconnected-(U$1-SPI_CLK-PadR23)") (class "Default")
      (node (ref "U$1") (pin "R23") (pinfunction "SPI_CLK_R23") (pintype "bidirectional"))
    )
    (net (code "110") (name "unconnected-(U$1-SPI_MISO-PadR21)") (class "Default")
      (node (ref "U$1") (pin "R21") (pinfunction "SPI_MISO_R21") (pintype "bidirectional"))
    )
    (net (code "111") (name "unconnected-(U$1-SPI_MOSI-PadR19)") (class "Default")
      (node (ref "U$1") (pin "R19") (pinfunction "SPI_MOSI_R19") (pintype "bidirectional"))
    )
    (net (code "112") (name "unconnected-(U$1-TXD0-PadR08)") (class "Default")
      (node (ref "U$1") (pin "R08") (pinfunction "TXD0_R08") (pintype "bidirectional"))
    )
    (net (code "113") (name "unconnected-(U6-ECG-ALRT{slash}RDY-Pad2)") (class "Default")
      (node (ref "U6-ECG") (pin "2") (pinfunction "ALRT/RDY_2") (pintype "output"))
    )
    (net (code "114") (name "unconnected-(U7-PO-ALRT{slash}RDY-Pad2)") (class "Default")
      (node (ref "U7-PO") (pin "2") (pinfunction "ALRT/RDY_2") (pintype "output"))
    )
    (net (code "115") (name "unconnected-(U9-X-Pad7)") (class "Default")
      (node (ref "U9") (pin "7") (pinfunction "X_7") (pintype "bidirectional"))
    )
    (net (code "116") (name "unconnected-(U10-X-Pad7)") (class "Default")
      (node (ref "U10") (pin "7") (pinfunction "X_7") (pintype "bidirectional"))
    )
  )
)
